# Soil_Moisture_Sensor_SMD-cr.net
KiCad netlist of a schematic drawn in EAGLE
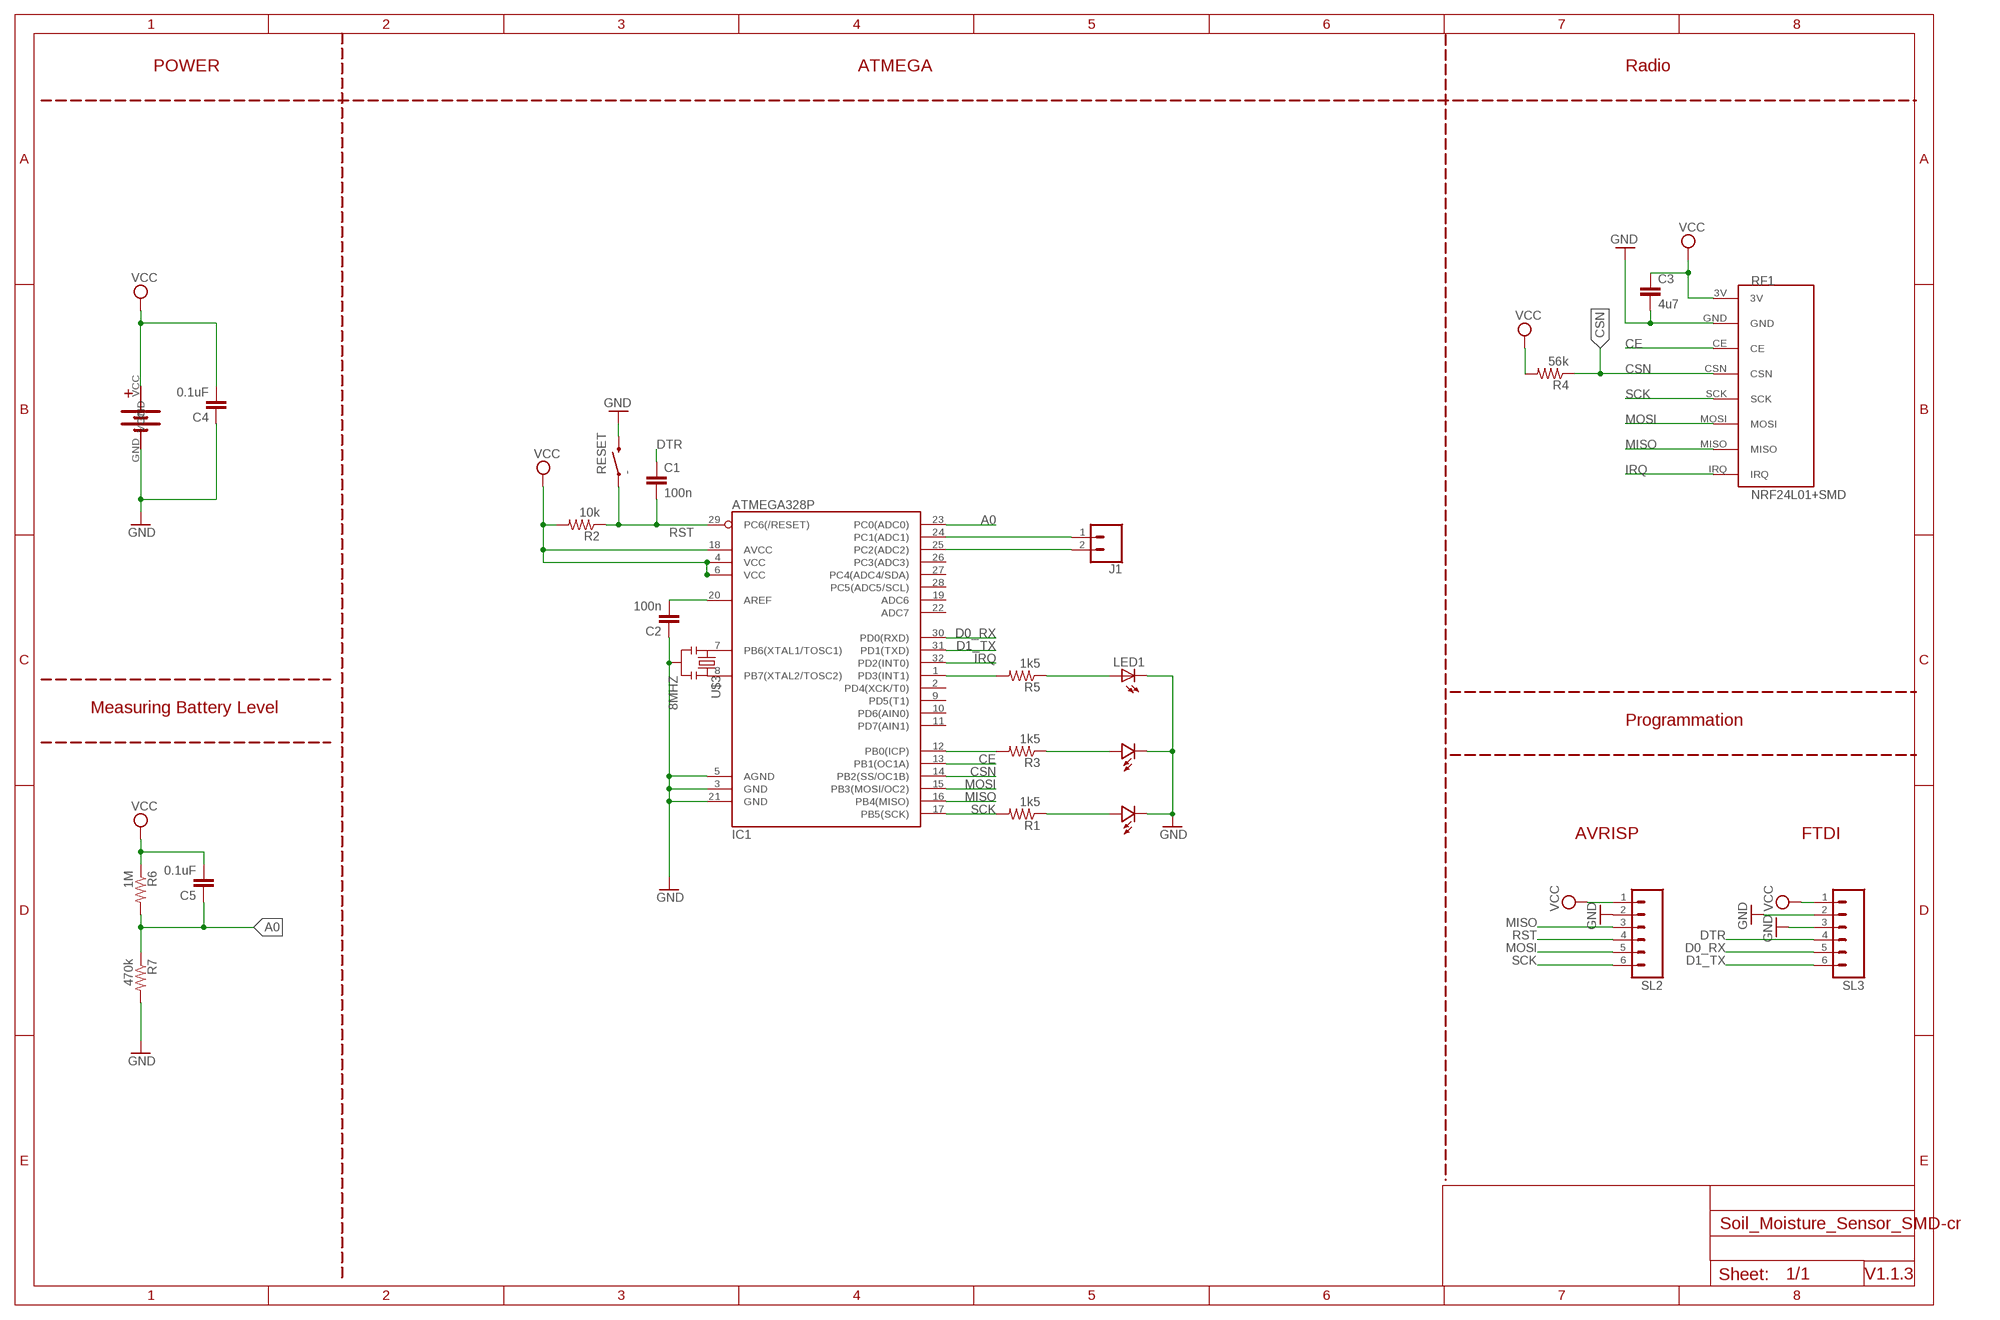
[diagram p0: schematic, sheet 1]

(export (version "E")
  (design (tool "Eeschema 10.0.6"))
  (components
    (comp (ref "C1")
      (value "100n")
      (footprint "eagle-import:0805-CAP")
      (libsource (lib "eagle-import") (part "CAP0805-CAP"))
    )
    (comp (ref "C2")
      (value "100n")
      (footprint "eagle-import:0805-CAP")
      (libsource (lib "eagle-import") (part "CAP0805-CAP"))
    )
    (comp (ref "C3")
      (value "4u7")
      (footprint "eagle-import:0805-CAP")
      (libsource (lib "eagle-import") (part "CAP0805-CAP"))
    )
    (comp (ref "C4")
      (value "0.1uF")
      (footprint "eagle-import:0805-CAP")
      (libsource (lib "eagle-import") (part "CAP0805-CAP"))
    )
    (comp (ref "C5")
      (value "0.1uF")
      (footprint "eagle-import:0805-CAP")
      (libsource (lib "eagle-import") (part "CAP0805-CAP"))
    )
    (comp (ref "D1")
      (value "LED0805")
      (footprint "eagle-import:0805-LED")
      (libsource (lib "eagle-import") (part "LED0805"))
    )
    (comp (ref "D2")
      (value "LED0805")
      (footprint "eagle-import:0805-LED")
      (libsource (lib "eagle-import") (part "LED0805"))
    )
    (comp (ref "IC1")
      (value "ATMEGA328P")
      (footprint "eagle-import:TQFP32-08")
      (libsource (lib "eagle-import") (part "ATMEGA168/328TQFP32"))
    )
    (comp (ref "J1")
      (value "CONN_02")
      (footprint "eagle-import:1X02")
      (libsource (lib "eagle-import") (part "CONN_02"))
    )
    (comp (ref "LED1")
      (value "LED5MM")
      (footprint "eagle-import:LED5MM")
      (libsource (lib "eagle-import") (part "LED5MM"))
    )
    (comp (ref "R1")
      (value "1k5")
      (footprint "eagle-import:0805-RES")
      (libsource (lib "eagle-import") (part "RESISTOR0805-RES"))
    )
    (comp (ref "R2")
      (value "10k")
      (footprint "eagle-import:0805-RES")
      (libsource (lib "eagle-import") (part "RESISTOR0805-RES"))
    )
    (comp (ref "R3")
      (value "1k5")
      (footprint "eagle-import:0805-RES")
      (libsource (lib "eagle-import") (part "RESISTOR0805-RES"))
    )
    (comp (ref "R4")
      (value "56k")
      (footprint "eagle-import:0805-RES")
      (libsource (lib "eagle-import") (part "RESISTOR0805-RES"))
    )
    (comp (ref "R5")
      (value "1k5")
      (footprint "eagle-import:0805-RES")
      (libsource (lib "eagle-import") (part "RESISTOR0805-RES"))
    )
    (comp (ref "R6")
      (value "1M")
      (footprint "eagle-import:0805-RES")
      (libsource (lib "eagle-import") (part "RESISTOR0805-RES"))
    )
    (comp (ref "R7")
      (value "470k")
      (footprint "eagle-import:0805-RES")
      (libsource (lib "eagle-import") (part "RESISTOR0805-RES"))
    )
    (comp (ref "RESET")
      (value "-")
      (footprint "eagle-import:TACTILE-SWITCH-1101NE")
      (libsource (lib "eagle-import") (part "SWITCH-MOMENTARY-2-SMD-1101NE"))
    )
    (comp (ref "RF1")
      (value "NRF24L01+SMD")
      (footprint "eagle-import:NRF24L01+SMD_MODULE")
      (libsource (lib "eagle-import") (part "NRF24L01+SMD_MODULE"))
    )
    (comp (ref "SL2")
      (value "M06SMD-1MM")
      (footprint "eagle-import:1X06-1MM")
      (libsource (lib "eagle-import") (part "M06SMD-1MM"))
    )
    (comp (ref "SL3")
      (value "M06SMD-1MM")
      (footprint "eagle-import:1X06-1MM")
      (libsource (lib "eagle-import") (part "M06SMD-1MM"))
    )
    (comp (ref "U$1")
      (value "CR123-BATTERYHOLDER")
      (footprint "eagle-import:CR123_BATTERYHOLDER")
      (libsource (lib "eagle-import") (part "CR123-BATTERYHOLDER"))
    )
    (comp (ref "U$3")
      (value "8MHZ")
      (footprint "eagle-import:RESONATOR-SMD")
      (libsource (lib "eagle-import") (part "RESONATORSMD"))
    )
  )
  (nets
    (net (code "1") (name "/CE") (class "Default")
      (node (ref "IC1") (pin "13") (pinfunction "PB1(OC1A)_13") (pintype "bidirectional"))
      (node (ref "RF1") (pin "CE") (pinfunction "CE_CE") (pintype "bidirectional"))
    )
    (net (code "2") (name "/D0_RX") (class "Default")
      (node (ref "IC1") (pin "30") (pinfunction "PD0(RXD)_30") (pintype "bidirectional"))
      (node (ref "SL3") (pin "5") (pinfunction "5_5") (pintype "passive"))
    )
    (net (code "3") (name "/D1_TX") (class "Default")
      (node (ref "IC1") (pin "31") (pinfunction "PD1(TXD)_31") (pintype "bidirectional"))
      (node (ref "SL3") (pin "6") (pinfunction "6_6") (pintype "passive"))
    )
    (net (code "4") (name "/DTR") (class "Default")
      (node (ref "C1") (pin "1") (pinfunction "1_1") (pintype "passive"))
      (node (ref "SL3") (pin "4") (pinfunction "4_4") (pintype "passive"))
    )
    (net (code "5") (name "/IRQ") (class "Default")
      (node (ref "IC1") (pin "32") (pinfunction "PD2(INT0)_32") (pintype "bidirectional"))
      (node (ref "RF1") (pin "IRQ") (pinfunction "IRQ_IRQ") (pintype "bidirectional"))
    )
    (net (code "6") (name "/MISO") (class "Default")
      (node (ref "IC1") (pin "16") (pinfunction "PB4(MISO)_16") (pintype "bidirectional"))
      (node (ref "RF1") (pin "MISO") (pinfunction "MISO_MISO") (pintype "bidirectional"))
      (node (ref "SL2") (pin "3") (pinfunction "3_3") (pintype "passive"))
    )
    (net (code "7") (name "/MOSI") (class "Default")
      (node (ref "IC1") (pin "15") (pinfunction "PB3(MOSI/OC2)_15") (pintype "bidirectional"))
      (node (ref "RF1") (pin "MOSI") (pinfunction "MOSI_MOSI") (pintype "bidirectional"))
      (node (ref "SL2") (pin "5") (pinfunction "5_5") (pintype "passive"))
    )
    (net (code "8") (name "/RST") (class "Default")
      (node (ref "C1") (pin "2") (pinfunction "2_2") (pintype "passive"))
      (node (ref "IC1") (pin "29") (pinfunction "PC6(/RESET)_29") (pintype "bidirectional"))
      (node (ref "R2") (pin "1") (pinfunction "1_1") (pintype "passive"))
      (node (ref "RESET") (pin "P$1") (pinfunction "1_P$1") (pintype "passive"))
      (node (ref "SL2") (pin "4") (pinfunction "4_4") (pintype "passive"))
    )
    (net (code "9") (name "/SCK") (class "Default")
      (node (ref "IC1") (pin "17") (pinfunction "PB5(SCK)_17") (pintype "bidirectional"))
      (node (ref "R1") (pin "2") (pinfunction "2_2") (pintype "passive"))
      (node (ref "RF1") (pin "SCK") (pinfunction "SCK_SCK") (pintype "bidirectional"))
      (node (ref "SL2") (pin "6") (pinfunction "6_6") (pintype "passive"))
    )
    (net (code "10") (name "A0") (class "Default")
      (node (ref "C5") (pin "1") (pinfunction "1_1") (pintype "passive"))
      (node (ref "IC1") (pin "23") (pinfunction "PC0(ADC0)_23") (pintype "bidirectional"))
      (node (ref "R6") (pin "2") (pinfunction "2_2") (pintype "passive"))
      (node (ref "R7") (pin "1") (pinfunction "1_1") (pintype "passive"))
    )
    (net (code "11") (name "CSN") (class "Default")
      (node (ref "IC1") (pin "14") (pinfunction "PB2(SS/OC1B)_14") (pintype "bidirectional"))
      (node (ref "R4") (pin "1") (pinfunction "1_1") (pintype "passive"))
      (node (ref "RF1") (pin "CSN") (pinfunction "CSN_CSN") (pintype "bidirectional"))
    )
    (net (code "12") (name "GND") (class "Default")
      (node (ref "C2") (pin "1") (pinfunction "1_1") (pintype "passive"))
      (node (ref "C3") (pin "2") (pinfunction "2_2") (pintype "passive"))
      (node (ref "C4") (pin "1") (pinfunction "1_1") (pintype "passive"))
      (node (ref "D1") (pin "MINUS") (pinfunction "MINUS_MINUS") (pintype "passive"))
      (node (ref "D2") (pin "MINUS") (pinfunction "MINUS_MINUS") (pintype "passive"))
      (node (ref "IC1") (pin "21") (pinfunction "GND_21") (pintype "bidirectional"))
      (node (ref "IC1") (pin "3") (pinfunction "GND_3") (pintype "bidirectional"))
      (node (ref "IC1") (pin "5") (pinfunction "AGND_5") (pintype "bidirectional"))
      (node (ref "LED1") (pin "K") (pinfunction "C_K") (pintype "passive"))
      (node (ref "R7") (pin "2") (pinfunction "2_2") (pintype "passive"))
      (node (ref "RESET") (pin "P$2") (pinfunction "2_P$2") (pintype "passive"))
      (node (ref "RF1") (pin "GND") (pinfunction "GND_GND") (pintype "bidirectional"))
      (node (ref "SL2") (pin "2") (pinfunction "2_2") (pintype "passive"))
      (node (ref "SL3") (pin "2") (pinfunction "2_2") (pintype "passive"))
      (node (ref "SL3") (pin "3") (pinfunction "3_3") (pintype "passive"))
      (node (ref "U$1") (pin "GND") (pinfunction "GND_GND") (pintype "passive"))
      (node (ref "U$3") (pin "2") (pinfunction "2_2") (pintype "passive"))
    )
    (net (code "13") (name "Net-(D1-PadPLUS)") (class "Default")
      (node (ref "D1") (pin "PLUS") (pinfunction "PLUS_PLUS") (pintype "passive"))
      (node (ref "R3") (pin "1") (pinfunction "1_1") (pintype "passive"))
    )
    (net (code "14") (name "Net-(D2-PadPLUS)") (class "Default")
      (node (ref "D2") (pin "PLUS") (pinfunction "PLUS_PLUS") (pintype "passive"))
      (node (ref "R1") (pin "1") (pinfunction "1_1") (pintype "passive"))
    )
    (net (code "15") (name "Net-(IC1-AREF)") (class "Default")
      (node (ref "C2") (pin "2") (pinfunction "2_2") (pintype "passive"))
      (node (ref "IC1") (pin "20") (pinfunction "AREF_20") (pintype "bidirectional"))
    )
    (net (code "16") (name "Net-(IC1-PB0(ICP))") (class "Default")
      (node (ref "IC1") (pin "12") (pinfunction "PB0(ICP)_12") (pintype "bidirectional"))
      (node (ref "R3") (pin "2") (pinfunction "2_2") (pintype "passive"))
    )
    (net (code "17") (name "Net-(IC1-PB6(XTAL1{slash}TOSC1))") (class "Default")
      (node (ref "IC1") (pin "7") (pinfunction "PB6(XTAL1/TOSC1)_7") (pintype "bidirectional"))
      (node (ref "U$3") (pin "1") (pinfunction "1_1") (pintype "passive"))
    )
    (net (code "18") (name "Net-(IC1-PB7(XTAL2{slash}TOSC2))") (class "Default")
      (node (ref "IC1") (pin "8") (pinfunction "PB7(XTAL2/TOSC2)_8") (pintype "bidirectional"))
      (node (ref "U$3") (pin "3") (pinfunction "3_3") (pintype "passive"))
    )
    (net (code "19") (name "Net-(IC1-PC1(ADC1))") (class "Default")
      (node (ref "IC1") (pin "24") (pinfunction "PC1(ADC1)_24") (pintype "bidirectional"))
      (node (ref "J1") (pin "1") (pinfunction "1_1") (pintype "passive"))
    )
    (net (code "20") (name "Net-(IC1-PC2(ADC2))") (class "Default")
      (node (ref "IC1") (pin "25") (pinfunction "PC2(ADC2)_25") (pintype "bidirectional"))
      (node (ref "J1") (pin "2") (pinfunction "2_2") (pintype "passive"))
    )
    (net (code "21") (name "Net-(IC1-PD3(INT1))") (class "Default")
      (node (ref "IC1") (pin "1") (pinfunction "PD3(INT1)_1") (pintype "bidirectional"))
      (node (ref "R5") (pin "2") (pinfunction "2_2") (pintype "passive"))
    )
    (net (code "22") (name "Net-(LED1-PadA)") (class "Default")
      (node (ref "LED1") (pin "A") (pinfunction "A_A") (pintype "passive"))
      (node (ref "R5") (pin "1") (pinfunction "1_1") (pintype "passive"))
    )
    (net (code "23") (name "VCC") (class "Default")
      (node (ref "C3") (pin "1") (pinfunction "1_1") (pintype "passive"))
      (node (ref "C4") (pin "2") (pinfunction "2_2") (pintype "passive"))
      (node (ref "C5") (pin "2") (pinfunction "2_2") (pintype "passive"))
      (node (ref "IC1") (pin "18") (pinfunction "AVCC_18") (pintype "bidirectional"))
      (node (ref "IC1") (pin "4") (pinfunction "VCC_4") (pintype "bidirectional"))
      (node (ref "IC1") (pin "6") (pinfunction "VCC_6") (pintype "bidirectional"))
      (node (ref "R2") (pin "2") (pinfunction "2_2") (pintype "passive"))
      (node (ref "R4") (pin "2") (pinfunction "2_2") (pintype "passive"))
      (node (ref "R6") (pin "1") (pinfunction "1_1") (pintype "passive"))
      (node (ref "RF1") (pin "3V") (pinfunction "3V_3V") (pintype "bidirectional"))
      (node (ref "SL2") (pin "1") (pinfunction "1_1") (pintype "passive"))
      (node (ref "SL3") (pin "1") (pinfunction "1_1") (pintype "passive"))
      (node (ref "U$1") (pin "VCC") (pinfunction "VCC_VCC") (pintype "passive"))
    )
    (net (code "24") (name "unconnected-(IC1-ADC6-Pad19)") (class "Default")
      (node (ref "IC1") (pin "19") (pinfunction "ADC6_19") (pintype "bidirectional"))
    )
    (net (code "25") (name "unconnected-(IC1-ADC7-Pad22)") (class "Default")
      (node (ref "IC1") (pin "22") (pinfunction "ADC7_22") (pintype "bidirectional"))
    )
    (net (code "26") (name "unconnected-(IC1-PC3(ADC3)-Pad26)") (class "Default")
      (node (ref "IC1") (pin "26") (pinfunction "PC3(ADC3)_26") (pintype "bidirectional"))
    )
    (net (code "27") (name "unconnected-(IC1-PC4(ADC4{slash}SDA)-Pad27)") (class "Default")
      (node (ref "IC1") (pin "27") (pinfunction "PC4(ADC4/SDA)_27") (pintype "bidirectional"))
    )
    (net (code "28") (name "unconnected-(IC1-PC5(ADC5{slash}SCL)-Pad28)") (class "Default")
      (node (ref "IC1") (pin "28") (pinfunction "PC5(ADC5/SCL)_28") (pintype "bidirectional"))
    )
    (net (code "29") (name "unconnected-(IC1-PD4(XCK{slash}T0)-Pad2)") (class "Default")
      (node (ref "IC1") (pin "2") (pinfunction "PD4(XCK/T0)_2") (pintype "bidirectional"))
    )
    (net (code "30") (name "unconnected-(IC1-PD5(T1)-Pad9)") (class "Default")
      (node (ref "IC1") (pin "9") (pinfunction "PD5(T1)_9") (pintype "bidirectional"))
    )
    (net (code "31") (name "unconnected-(IC1-PD6(AIN0)-Pad10)") (class "Default")
      (node (ref "IC1") (pin "10") (pinfunction "PD6(AIN0)_10") (pintype "bidirectional"))
    )
    (net (code "32") (name "unconnected-(IC1-PD7(AIN1)-Pad11)") (class "Default")
      (node (ref "IC1") (pin "11") (pinfunction "PD7(AIN1)_11") (pintype "bidirectional"))
    )
  )
)
